# BUDDY_BEST_1.net
KiCad netlist of a schematic drawn in EAGLE
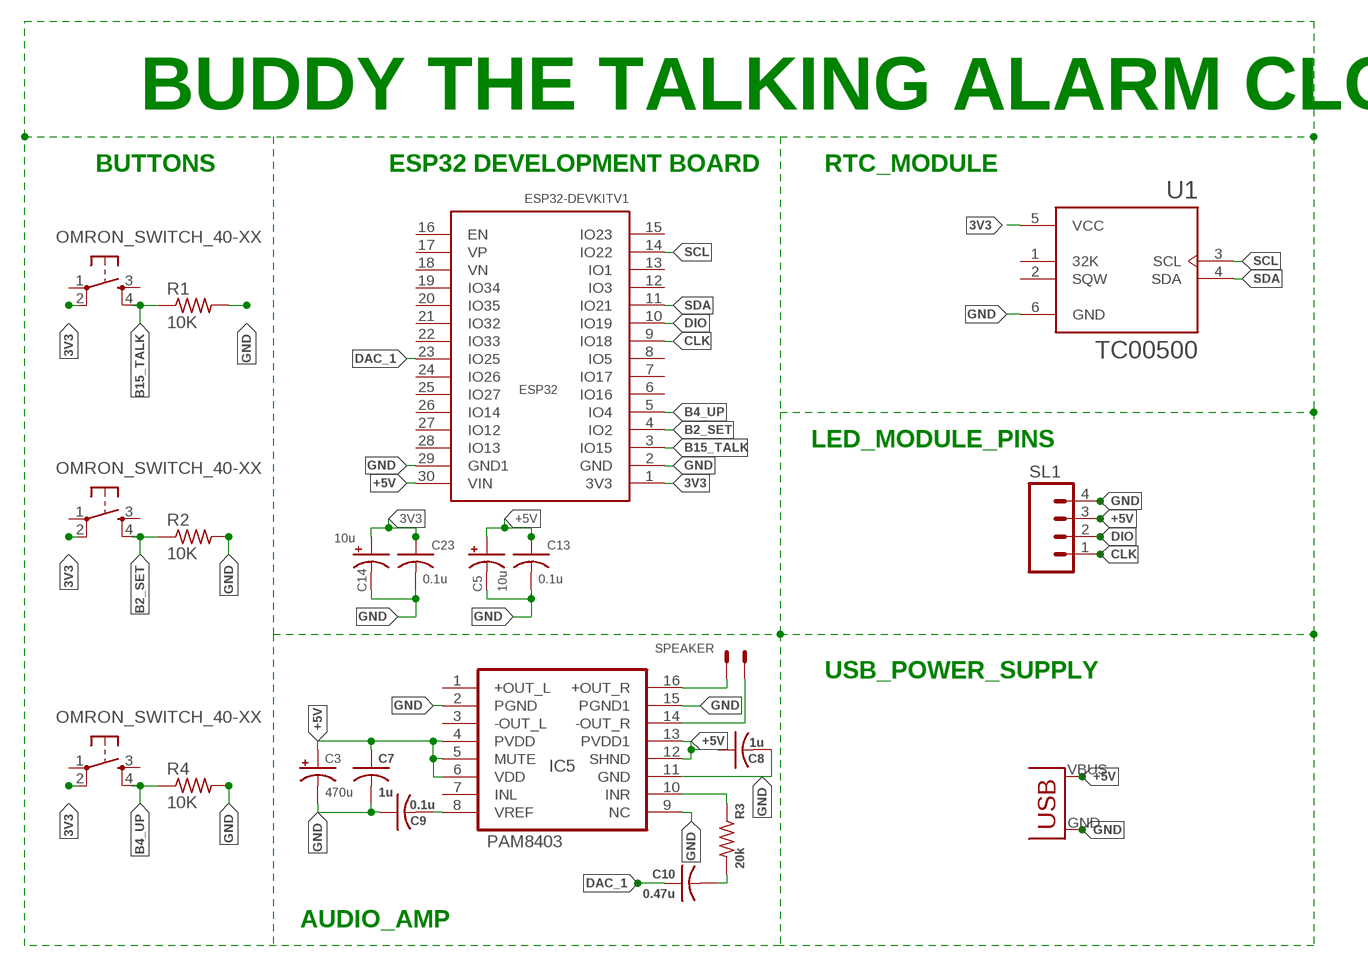
[diagram p0: schematic, sheet 1]

(export (version "E")
  (design (tool "Eeschema 10.0.6"))
  (components
    (comp (ref "C3")
      (value "470u")
      (footprint "eagle-import:E5-10,5")
      (libsource (lib "eagle-import") (part "CPOL-USE5-10.5"))
    )
    (comp (ref "C5")
      (value "10u")
      (footprint "eagle-import:E2,5-5")
      (libsource (lib "eagle-import") (part "CPOL-USE2.5-5"))
    )
    (comp (ref "C7")
      (value "1u")
      (footprint "eagle-import:C0805")
      (libsource (lib "eagle-import") (part "CAP0805"))
    )
    (comp (ref "C8")
      (value "1u")
      (footprint "eagle-import:C0805")
      (libsource (lib "eagle-import") (part "CAP0805"))
    )
    (comp (ref "C9")
      (value "0.1u")
      (footprint "eagle-import:C0805")
      (libsource (lib "eagle-import") (part "CAP0805"))
    )
    (comp (ref "C10")
      (value "0.47u")
      (footprint "eagle-import:C0603")
      (libsource (lib "eagle-import") (part "CAP0603"))
    )
    (comp (ref "C13")
      (value "0.1u")
      (footprint "eagle-import:C025-024X044")
      (libsource (lib "eagle-import") (part "C-US025-024X044"))
    )
    (comp (ref "C14")
      (value "10u")
      (footprint "eagle-import:E2,5-5")
      (libsource (lib "eagle-import") (part "CPOL-USE2.5-5"))
    )
    (comp (ref "C23")
      (value "0.1u")
      (footprint "eagle-import:C025-024X044")
      (libsource (lib "eagle-import") (part "C-US025-024X044"))
    )
    (comp (ref "ESP32")
      (value "ESP32-DEVKITV1_ESP32DEVKITV1ESP32")
      (footprint "eagle-import:ESP32")
      (libsource (lib "eagle-import") (part "ESP32-DEVKITV1_ESP32DEVKITV1ESP32"))
    )
    (comp (ref "IC5")
      (value "PAM8403")
      (footprint "eagle-import:SOP-16")
      (libsource (lib "eagle-import") (part "PAM8403"))
    )
    (comp (ref "R1")
      (value "10K")
      (footprint "eagle-import:0207_10")
      (libsource (lib "eagle-import") (part "RESISTOR0207/10"))
    )
    (comp (ref "R2")
      (value "10K")
      (footprint "eagle-import:0207_10")
      (libsource (lib "eagle-import") (part "RESISTOR0207/10"))
    )
    (comp (ref "R3")
      (value "20k")
      (footprint "eagle-import:0207_10")
      (libsource (lib "eagle-import") (part "R-US_0207/10"))
    )
    (comp (ref "R4")
      (value "10K")
      (footprint "eagle-import:0207_10")
      (libsource (lib "eagle-import") (part "RESISTOR0207/10"))
    )
    (comp (ref "SL1")
      (value "M04")
      (footprint "eagle-import:04P")
      (libsource (lib "eagle-import") (part "M04"))
    )
    (comp (ref "SPEAKER")
      (value "SPEAKER")
      (footprint "eagle-import:JST-XH-02-PACKAGE-LONG-PAD")
      (libsource (lib "eagle-import") (part "JST-XH-02-PIN-LONG-PAD"))
    )
    (comp (ref "U$1")
      (value "OMRON_SWITCH_40-XX")
      (footprint "eagle-import:B3F-40XX")
      (libsource (lib "eagle-import") (part "OMRON_SWITCH_40-XX"))
    )
    (comp (ref "U$2")
      (value "OMRON_SWITCH_40-XX")
      (footprint "eagle-import:B3F-40XX")
      (libsource (lib "eagle-import") (part "OMRON_SWITCH_40-XX"))
    )
    (comp (ref "U$3")
      (value "OMRON_SWITCH_40-XX")
      (footprint "eagle-import:B3F-40XX")
      (libsource (lib "eagle-import") (part "OMRON_SWITCH_40-XX"))
    )
    (comp (ref "U$5")
      (value "USB(POWER)")
      (footprint "eagle-import:USB(POWER)")
      (libsource (lib "eagle-import") (part "USB(POWER)"))
    )
    (comp (ref "U1")
      (value "TC00500")
      (footprint "eagle-import:MODULE_TC00500")
      (fields (field (name "MF") "YKS"))
      (libsource (lib "eagle-import") (part "TC00500"))
    )
  )
  (nets
    (net (code "1") (name "+5V") (class "Default")
      (node (ref "C13") (pin "1") (pinfunction "1_1") (pintype "passive"))
      (node (ref "C3") (pin "+") (pinfunction "+_+") (pintype "passive"))
      (node (ref "C5") (pin "+") (pinfunction "+_+") (pintype "passive"))
      (node (ref "C7") (pin "1") (pinfunction "1_1") (pintype "passive"))
      (node (ref "C8") (pin "1") (pinfunction "1_1") (pintype "passive"))
      (node (ref "ESP32") (pin "30") (pinfunction "VIN_30") (pintype "bidirectional"))
      (node (ref "IC5") (pin "12") (pinfunction "SHND_12") (pintype "output"))
      (node (ref "IC5") (pin "13") (pinfunction "PVDD1_13") (pintype "output"))
      (node (ref "IC5") (pin "4") (pinfunction "PVDD_4") (pintype "input"))
      (node (ref "IC5") (pin "5") (pinfunction "MUTE_5") (pintype "input"))
      (node (ref "IC5") (pin "6") (pinfunction "VDD_6") (pintype "input"))
      (node (ref "SL1") (pin "3") (pinfunction "3_3") (pintype "passive"))
      (node (ref "U$5") (pin "VBUS") (pinfunction "VCC_VBUS") (pintype "power_in"))
    )
    (net (code "2") (name "3V3") (class "Default")
      (node (ref "C14") (pin "+") (pinfunction "+_+") (pintype "passive"))
      (node (ref "C23") (pin "1") (pinfunction "1_1") (pintype "passive"))
      (node (ref "ESP32") (pin "1") (pinfunction "3V3_1") (pintype "bidirectional"))
      (node (ref "U$1") (pin "2") (pinfunction "P1_2") (pintype "passive"))
      (node (ref "U$2") (pin "2") (pinfunction "P1_2") (pintype "passive"))
      (node (ref "U$3") (pin "2") (pinfunction "P1_2") (pintype "passive"))
      (node (ref "U1") (pin "5") (pinfunction "VCC_5") (pintype "power_in"))
    )
    (net (code "3") (name "B2_SET") (class "Default")
      (node (ref "ESP32") (pin "4") (pinfunction "IO2_4") (pintype "bidirectional"))
      (node (ref "R2") (pin "1") (pinfunction "1_1") (pintype "passive"))
      (node (ref "U$1") (pin "4") (pinfunction "S1_4") (pintype "passive"))
    )
    (net (code "4") (name "B4_UP") (class "Default")
      (node (ref "ESP32") (pin "5") (pinfunction "IO4_5") (pintype "bidirectional"))
      (node (ref "R4") (pin "1") (pinfunction "1_1") (pintype "passive"))
      (node (ref "U$3") (pin "4") (pinfunction "S1_4") (pintype "passive"))
    )
    (net (code "5") (name "B15_TALK") (class "Default")
      (node (ref "ESP32") (pin "3") (pinfunction "IO15_3") (pintype "bidirectional"))
      (node (ref "R1") (pin "1") (pinfunction "1_1") (pintype "passive"))
      (node (ref "U$2") (pin "4") (pinfunction "S1_4") (pintype "passive"))
    )
    (net (code "6") (name "CLK") (class "Default")
      (node (ref "ESP32") (pin "9") (pinfunction "IO18_9") (pintype "bidirectional"))
      (node (ref "SL1") (pin "1") (pinfunction "1_1") (pintype "passive"))
    )
    (net (code "7") (name "DAC_1") (class "Default")
      (node (ref "C10") (pin "1") (pinfunction "1_1") (pintype "passive"))
      (node (ref "ESP32") (pin "23") (pinfunction "IO25_23") (pintype "bidirectional"))
    )
    (net (code "8") (name "DIO") (class "Default")
      (node (ref "ESP32") (pin "10") (pinfunction "IO19_10") (pintype "bidirectional"))
      (node (ref "SL1") (pin "2") (pinfunction "2_2") (pintype "passive"))
    )
    (net (code "9") (name "GND") (class "Default")
      (node (ref "C13") (pin "2") (pinfunction "2_2") (pintype "passive"))
      (node (ref "C14") (pin "-") (pinfunction "-_-") (pintype "passive"))
      (node (ref "C23") (pin "2") (pinfunction "2_2") (pintype "passive"))
      (node (ref "C3") (pin "-") (pinfunction "-_-") (pintype "passive"))
      (node (ref "C5") (pin "-") (pinfunction "-_-") (pintype "passive"))
      (node (ref "C7") (pin "2") (pinfunction "2_2") (pintype "passive"))
      (node (ref "C8") (pin "2") (pinfunction "2_2") (pintype "passive"))
      (node (ref "C9") (pin "1") (pinfunction "1_1") (pintype "passive"))
      (node (ref "ESP32") (pin "2") (pinfunction "GND_2") (pintype "bidirectional"))
      (node (ref "ESP32") (pin "29") (pinfunction "GND1_29") (pintype "bidirectional"))
      (node (ref "IC5") (pin "11") (pinfunction "GND_11") (pintype "output"))
      (node (ref "IC5") (pin "15") (pinfunction "PGND1_15") (pintype "output"))
      (node (ref "IC5") (pin "2") (pinfunction "PGND_2") (pintype "input"))
      (node (ref "IC5") (pin "9") (pinfunction "NC_9") (pintype "output"))
      (node (ref "R1") (pin "2") (pinfunction "2_2") (pintype "passive"))
      (node (ref "R2") (pin "2") (pinfunction "2_2") (pintype "passive"))
      (node (ref "R4") (pin "2") (pinfunction "2_2") (pintype "passive"))
      (node (ref "SL1") (pin "4") (pinfunction "4_4") (pintype "passive"))
      (node (ref "U$5") (pin "GND") (pinfunction "GND_GND") (pintype "power_in"))
      (node (ref "U1") (pin "6") (pinfunction "GND_6") (pintype "power_in"))
    )
    (net (code "10") (name "Net-(C10-Pad2)") (class "Default")
      (node (ref "C10") (pin "2") (pinfunction "2_2") (pintype "passive"))
      (node (ref "R3") (pin "2") (pinfunction "2_2") (pintype "passive"))
    )
    (net (code "11") (name "Net-(IC5-+OUT_R)") (class "Default")
      (node (ref "IC5") (pin "16") (pinfunction "+OUT_R_16") (pintype "output"))
      (node (ref "SPEAKER") (pin "2") (pinfunction "S_2") (pintype "passive"))
    )
    (net (code "12") (name "Net-(IC5--OUT_R)") (class "Default")
      (node (ref "IC5") (pin "14") (pinfunction "-OUT_R_14") (pintype "output"))
      (node (ref "SPEAKER") (pin "1") (pinfunction "S_1") (pintype "passive"))
    )
    (net (code "13") (name "Net-(IC5-INR)") (class "Default")
      (node (ref "IC5") (pin "10") (pinfunction "INR_10") (pintype "output"))
      (node (ref "R3") (pin "1") (pinfunction "1_1") (pintype "passive"))
    )
    (net (code "14") (name "Net-(IC5-VREF)") (class "Default")
      (node (ref "C9") (pin "2") (pinfunction "2_2") (pintype "passive"))
      (node (ref "IC5") (pin "8") (pinfunction "VREF_8") (pintype "input"))
    )
    (net (code "15") (name "SCL") (class "Default")
      (node (ref "ESP32") (pin "14") (pinfunction "IO22_14") (pintype "bidirectional"))
      (node (ref "U1") (pin "3") (pinfunction "SCL_3") (pintype "input"))
    )
    (net (code "16") (name "SDA") (class "Default")
      (node (ref "ESP32") (pin "11") (pinfunction "IO21_11") (pintype "bidirectional"))
      (node (ref "U1") (pin "4") (pinfunction "SDA_4") (pintype "bidirectional"))
    )
    (net (code "17") (name "unconnected-(ESP32-EN-Pad16)") (class "Default")
      (node (ref "ESP32") (pin "16") (pinfunction "EN_16") (pintype "bidirectional"))
    )
    (net (code "18") (name "unconnected-(ESP32-IO1-Pad13)") (class "Default")
      (node (ref "ESP32") (pin "13") (pinfunction "IO1_13") (pintype "bidirectional"))
    )
    (net (code "19") (name "unconnected-(ESP32-IO3-Pad12)") (class "Default")
      (node (ref "ESP32") (pin "12") (pinfunction "IO3_12") (pintype "bidirectional"))
    )
    (net (code "20") (name "unconnected-(ESP32-IO5-Pad8)") (class "Default")
      (node (ref "ESP32") (pin "8") (pinfunction "IO5_8") (pintype "bidirectional"))
    )
    (net (code "21") (name "unconnected-(ESP32-IO12-Pad27)") (class "Default")
      (node (ref "ESP32") (pin "27") (pinfunction "IO12_27") (pintype "bidirectional"))
    )
    (net (code "22") (name "unconnected-(ESP32-IO13-Pad28)") (class "Default")
      (node (ref "ESP32") (pin "28") (pinfunction "IO13_28") (pintype "bidirectional"))
    )
    (net (code "23") (name "unconnected-(ESP32-IO14-Pad26)") (class "Default")
      (node (ref "ESP32") (pin "26") (pinfunction "IO14_26") (pintype "bidirectional"))
    )
    (net (code "24") (name "unconnected-(ESP32-IO16-Pad6)") (class "Default")
      (node (ref "ESP32") (pin "6") (pinfunction "IO16_6") (pintype "bidirectional"))
    )
    (net (code "25") (name "unconnected-(ESP32-IO17-Pad7)") (class "Default")
      (node (ref "ESP32") (pin "7") (pinfunction "IO17_7") (pintype "bidirectional"))
    )
    (net (code "26") (name "unconnected-(ESP32-IO23-Pad15)") (class "Default")
      (node (ref "ESP32") (pin "15") (pinfunction "IO23_15") (pintype "bidirectional"))
    )
    (net (code "27") (name "unconnected-(ESP32-IO26-Pad24)") (class "Default")
      (node (ref "ESP32") (pin "24") (pinfunction "IO26_24") (pintype "bidirectional"))
    )
    (net (code "28") (name "unconnected-(ESP32-IO27-Pad25)") (class "Default")
      (node (ref "ESP32") (pin "25") (pinfunction "IO27_25") (pintype "bidirectional"))
    )
    (net (code "29") (name "unconnected-(ESP32-IO32-Pad21)") (class "Default")
      (node (ref "ESP32") (pin "21") (pinfunction "IO32_21") (pintype "bidirectional"))
    )
    (net (code "30") (name "unconnected-(ESP32-IO33-Pad22)") (class "Default")
      (node (ref "ESP32") (pin "22") (pinfunction "IO33_22") (pintype "bidirectional"))
    )
    (net (code "31") (name "unconnected-(ESP32-IO34-Pad19)") (class "Default")
      (node (ref "ESP32") (pin "19") (pinfunction "IO34_19") (pintype "bidirectional"))
    )
    (net (code "32") (name "unconnected-(ESP32-IO35-Pad20)") (class "Default")
      (node (ref "ESP32") (pin "20") (pinfunction "IO35_20") (pintype "bidirectional"))
    )
    (net (code "33") (name "unconnected-(ESP32-VN-Pad18)") (class "Default")
      (node (ref "ESP32") (pin "18") (pinfunction "VN_18") (pintype "bidirectional"))
    )
    (net (code "34") (name "unconnected-(ESP32-VP-Pad17)") (class "Default")
      (node (ref "ESP32") (pin "17") (pinfunction "VP_17") (pintype "bidirectional"))
    )
    (net (code "35") (name "unconnected-(IC5-+OUT_L-Pad1)") (class "Default")
      (node (ref "IC5") (pin "1") (pinfunction "+OUT_L_1") (pintype "input"))
    )
    (net (code "36") (name "unconnected-(IC5--OUT_L-Pad3)") (class "Default")
      (node (ref "IC5") (pin "3") (pinfunction "-OUT_L_3") (pintype "input"))
    )
    (net (code "37") (name "unconnected-(IC5-INL-Pad7)") (class "Default")
      (node (ref "IC5") (pin "7") (pinfunction "INL_7") (pintype "input"))
    )
    (net (code "38") (name "unconnected-(U$1-P-Pad1)") (class "Default")
      (node (ref "U$1") (pin "1") (pinfunction "P_1") (pintype "passive"))
    )
    (net (code "39") (name "unconnected-(U$1-S-Pad3)") (class "Default")
      (node (ref "U$1") (pin "3") (pinfunction "S_3") (pintype "passive"))
    )
    (net (code "40") (name "unconnected-(U$2-P-Pad1)") (class "Default")
      (node (ref "U$2") (pin "1") (pinfunction "P_1") (pintype "passive"))
    )
    (net (code "41") (name "unconnected-(U$2-S-Pad3)") (class "Default")
      (node (ref "U$2") (pin "3") (pinfunction "S_3") (pintype "passive"))
    )
    (net (code "42") (name "unconnected-(U$3-P-Pad1)") (class "Default")
      (node (ref "U$3") (pin "1") (pinfunction "P_1") (pintype "passive"))
    )
    (net (code "43") (name "unconnected-(U$3-S-Pad3)") (class "Default")
      (node (ref "U$3") (pin "3") (pinfunction "S_3") (pintype "passive"))
    )
    (net (code "44") (name "unconnected-(U1-32K-Pad1)") (class "Default")
      (node (ref "U1") (pin "1") (pinfunction "32K_1") (pintype "output"))
    )
    (net (code "45") (name "unconnected-(U1-SQW-Pad2)") (class "Default")
      (node (ref "U1") (pin "2") (pinfunction "SQW_2") (pintype "output"))
    )
  )
)
